# ardustat_discreet_resistors.net
KiCad netlist of a schematic drawn in EAGLE
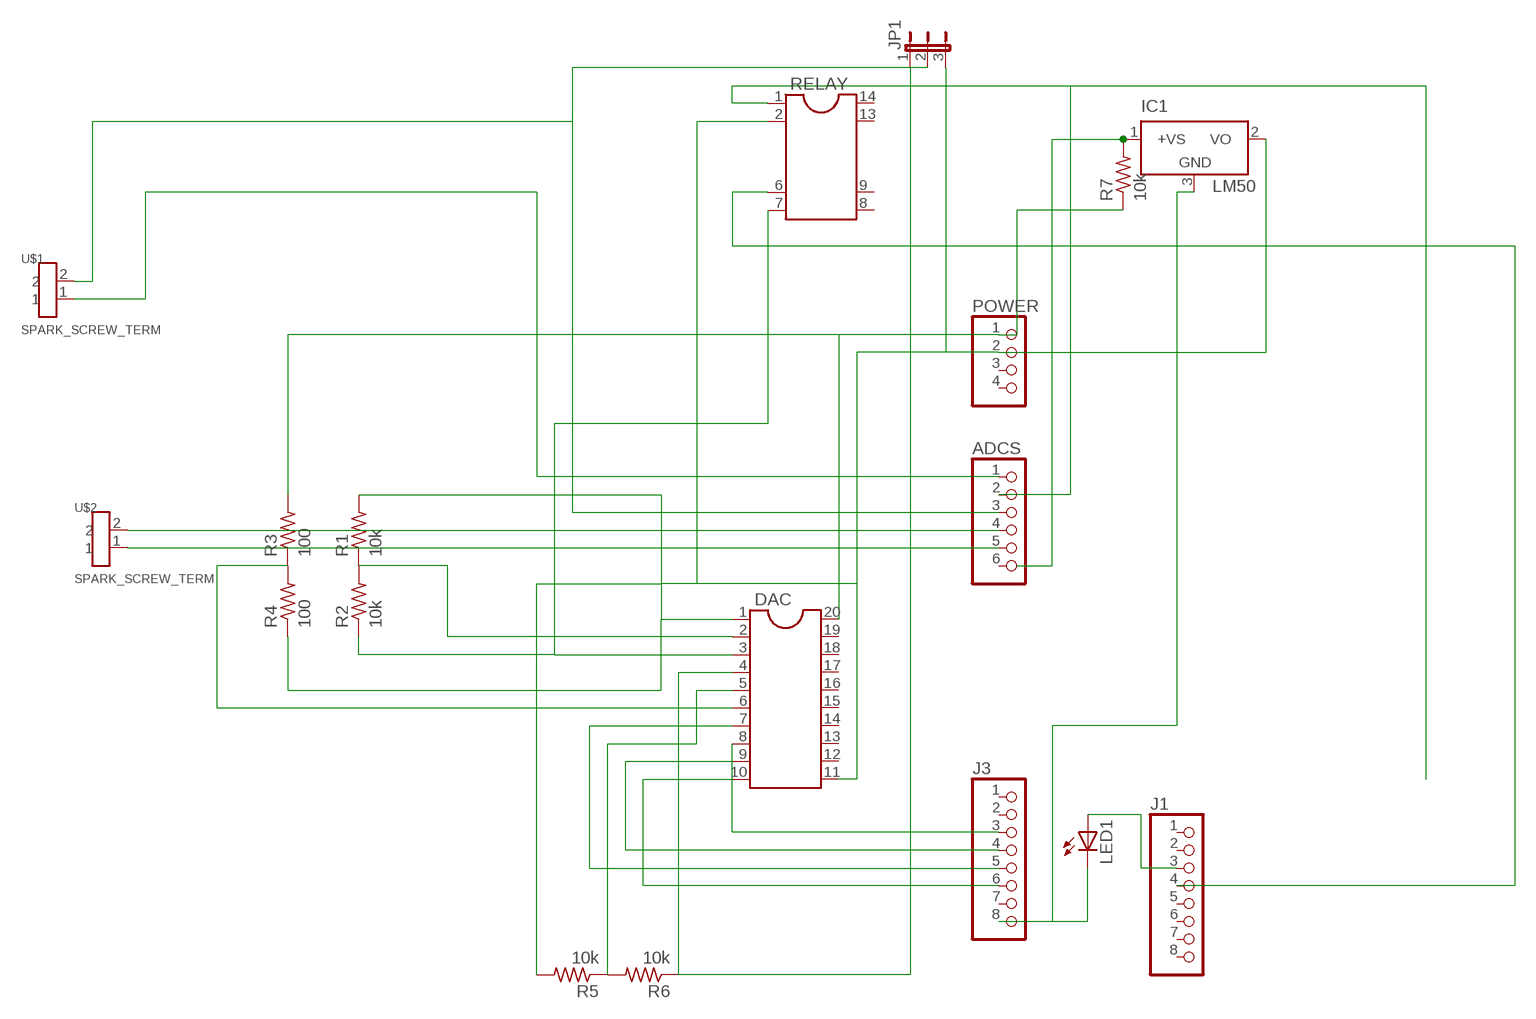
[diagram p0: schematic, sheet 1]

(export (version "E")
  (design (tool "Eeschema 10.0.6"))
  (components
    (comp (ref "ADCS")
      (value "PINHD-1X6")
      (footprint "eagle-import:1X06")
      (libsource (lib "eagle-import") (part "PINHD-1X6"))
    )
    (comp (ref "DAC")
      (value "DIL20S")
      (footprint "eagle-import:SOCKED-20")
      (libsource (lib "eagle-import") (part "DIL20S"))
    )
    (comp (ref "IC1")
      (value "LM50")
      (footprint "eagle-import:SOT23")
      (libsource (lib "eagle-import") (part "LM50"))
    )
    (comp (ref "J1")
      (value "PINHD-1X8")
      (footprint "eagle-import:1X08")
      (libsource (lib "eagle-import") (part "PINHD-1X8"))
    )
    (comp (ref "J3")
      (value "PINHD-1X8")
      (footprint "eagle-import:1X08")
      (libsource (lib "eagle-import") (part "PINHD-1X8"))
    )
    (comp (ref "JP1")
      (value "JP2E")
      (footprint "eagle-import:JP2")
      (libsource (lib "eagle-import") (part "JP2E"))
    )
    (comp (ref "LED1")
      (value "LED5MM")
      (footprint "eagle-import:LED5MM")
      (libsource (lib "eagle-import") (part "LED5MM"))
    )
    (comp (ref "POWER")
      (value "PINHD-1X4")
      (footprint "eagle-import:1X04")
      (libsource (lib "eagle-import") (part "PINHD-1X4"))
    )
    (comp (ref "R1")
      (value "10k")
      (footprint "eagle-import:0207_12")
      (libsource (lib "eagle-import") (part "R-US_0207/12"))
    )
    (comp (ref "R2")
      (value "10k")
      (footprint "eagle-import:0207_12")
      (libsource (lib "eagle-import") (part "R-US_0207/12"))
    )
    (comp (ref "R3")
      (value "100")
      (footprint "eagle-import:0207_12")
      (libsource (lib "eagle-import") (part "R-US_0207/12"))
    )
    (comp (ref "R4")
      (value "100")
      (footprint "eagle-import:0207_12")
      (libsource (lib "eagle-import") (part "R-US_0207/12"))
    )
    (comp (ref "R5")
      (value "10k")
      (footprint "eagle-import:0207_12")
      (libsource (lib "eagle-import") (part "R-US_0207/12"))
    )
    (comp (ref "R6")
      (value "10k")
      (footprint "eagle-import:0207_12")
      (libsource (lib "eagle-import") (part "R-US_0207/12"))
    )
    (comp (ref "R7")
      (value "10k")
      (footprint "eagle-import:0207_12")
      (libsource (lib "eagle-import") (part "R-US_0207/12"))
    )
    (comp (ref "RELAY")
      (value "DIL14/8")
      (footprint "eagle-import:DIL14_8")
      (libsource (lib "eagle-import") (part "DIL14/8"))
    )
    (comp (ref "U$1")
      (value "SPARK_SCREW_TERM")
      (footprint "eagle-import:SPARK_SCREW_TERM")
      (libsource (lib "eagle-import") (part "SPARK_SCREW_TERM"))
    )
    (comp (ref "U$2")
      (value "SPARK_SCREW_TERM")
      (footprint "eagle-import:SPARK_SCREW_TERM")
      (libsource (lib "eagle-import") (part "SPARK_SCREW_TERM"))
    )
  )
  (nets
    (net (code "1") (name "Net-(ADCS-Pad1)") (class "Default")
      (node (ref "ADCS") (pin "1") (pinfunction "1_1") (pintype "passive"))
      (node (ref "U$1") (pin "1") (pinfunction "1_1") (pintype "bidirectional"))
    )
    (net (code "2") (name "Net-(ADCS-Pad2)") (class "Default")
      (node (ref "ADCS") (pin "2") (pinfunction "2_2") (pintype "passive"))
      (node (ref "RELAY") (pin "1") (pinfunction "1_1") (pintype "passive"))
    )
    (net (code "3") (name "Net-(ADCS-Pad3)") (class "Default")
      (node (ref "ADCS") (pin "3") (pinfunction "3_3") (pintype "passive"))
      (node (ref "JP1") (pin "2") (pinfunction "2_2") (pintype "passive"))
      (node (ref "U$1") (pin "2") (pinfunction "2_2") (pintype "bidirectional"))
    )
    (net (code "4") (name "Net-(ADCS-Pad4)") (class "Default")
      (node (ref "ADCS") (pin "4") (pinfunction "4_4") (pintype "passive"))
      (node (ref "U$2") (pin "2") (pinfunction "2_2") (pintype "bidirectional"))
    )
    (net (code "5") (name "Net-(ADCS-Pad5)") (class "Default")
      (node (ref "ADCS") (pin "5") (pinfunction "5_5") (pintype "passive"))
      (node (ref "U$2") (pin "1") (pinfunction "1_1") (pintype "bidirectional"))
    )
    (net (code "6") (name "Net-(DAC-Pad2)") (class "Default")
      (node (ref "DAC") (pin "2") (pinfunction "2_2") (pintype "passive"))
      (node (ref "R1") (pin "1") (pinfunction "1_1") (pintype "passive"))
      (node (ref "R2") (pin "2") (pinfunction "2_2") (pintype "passive"))
    )
    (net (code "7") (name "Net-(DAC-Pad3)") (class "Default")
      (node (ref "DAC") (pin "3") (pinfunction "3_3") (pintype "passive"))
      (node (ref "R2") (pin "1") (pinfunction "1_1") (pintype "passive"))
      (node (ref "RELAY") (pin "7") (pinfunction "7_7") (pintype "passive"))
    )
    (net (code "8") (name "Net-(DAC-Pad4)") (class "Default")
      (node (ref "DAC") (pin "4") (pinfunction "4_4") (pintype "passive"))
      (node (ref "JP1") (pin "1") (pinfunction "1_1") (pintype "passive"))
      (node (ref "R6") (pin "1") (pinfunction "1_1") (pintype "passive"))
    )
    (net (code "9") (name "Net-(DAC-Pad5)") (class "Default")
      (node (ref "DAC") (pin "5") (pinfunction "5_5") (pintype "passive"))
      (node (ref "R5") (pin "1") (pinfunction "1_1") (pintype "passive"))
      (node (ref "R6") (pin "2") (pinfunction "2_2") (pintype "passive"))
    )
    (net (code "10") (name "Net-(DAC-Pad6)") (class "Default")
      (node (ref "DAC") (pin "6") (pinfunction "6_6") (pintype "passive"))
      (node (ref "R3") (pin "1") (pinfunction "1_1") (pintype "passive"))
      (node (ref "R4") (pin "2") (pinfunction "2_2") (pintype "passive"))
    )
    (net (code "11") (name "Net-(DAC-Pad7)") (class "Default")
      (node (ref "DAC") (pin "7") (pinfunction "7_7") (pintype "passive"))
      (node (ref "J3") (pin "5") (pinfunction "5_5") (pintype "passive"))
    )
    (net (code "12") (name "Net-(DAC-Pad8)") (class "Default")
      (node (ref "DAC") (pin "8") (pinfunction "8_8") (pintype "passive"))
      (node (ref "J3") (pin "3") (pinfunction "3_3") (pintype "passive"))
    )
    (net (code "13") (name "Net-(DAC-Pad9)") (class "Default")
      (node (ref "DAC") (pin "9") (pinfunction "9_9") (pintype "passive"))
      (node (ref "J3") (pin "4") (pinfunction "4_4") (pintype "passive"))
    )
    (net (code "14") (name "Net-(DAC-Pad10)") (class "Default")
      (node (ref "DAC") (pin "10") (pinfunction "10_10") (pintype "passive"))
      (node (ref "J3") (pin "6") (pinfunction "6_6") (pintype "passive"))
    )
    (net (code "15") (name "Net-(DAC-Pad20)") (class "Default")
      (node (ref "DAC") (pin "20") (pinfunction "20_20") (pintype "passive"))
      (node (ref "POWER") (pin "1") (pinfunction "1_1") (pintype "passive"))
      (node (ref "R3") (pin "2") (pinfunction "2_2") (pintype "passive"))
      (node (ref "R7") (pin "1") (pinfunction "1_1") (pintype "passive"))
    )
    (net (code "16") (name "Net-(IC1-+VS)") (class "Default")
      (node (ref "IC1") (pin "1") (pinfunction "+VS_1") (pintype "input"))
      (node (ref "R7") (pin "2") (pinfunction "2_2") (pintype "passive"))
    )
    (net (code "17") (name "Net-(IC1-GND)") (class "Default")
      (node (ref "IC1") (pin "3") (pinfunction "GND_3") (pintype "power_in"))
      (node (ref "J3") (pin "8") (pinfunction "8_8") (pintype "passive"))
      (node (ref "LED1") (pin "K") (pinfunction "C_K") (pintype "passive"))
    )
    (net (code "18") (name "Net-(IC1-VO)") (class "Default")
      (node (ref "DAC") (pin "1") (pinfunction "1_1") (pintype "passive"))
      (node (ref "DAC") (pin "11") (pinfunction "11_11") (pintype "passive"))
      (node (ref "IC1") (pin "2") (pinfunction "VO_2") (pintype "input"))
      (node (ref "JP1") (pin "3") (pinfunction "3_3") (pintype "passive"))
      (node (ref "POWER") (pin "2") (pinfunction "2_2") (pintype "passive"))
      (node (ref "R1") (pin "2") (pinfunction "2_2") (pintype "passive"))
      (node (ref "R4") (pin "1") (pinfunction "1_1") (pintype "passive"))
      (node (ref "R5") (pin "2") (pinfunction "2_2") (pintype "passive"))
      (node (ref "RELAY") (pin "2") (pinfunction "2_2") (pintype "passive"))
    )
    (net (code "19") (name "Net-(J1-Pad3)") (class "Default")
      (node (ref "J1") (pin "3") (pinfunction "3_3") (pintype "passive"))
      (node (ref "LED1") (pin "A") (pinfunction "A_A") (pintype "passive"))
    )
    (net (code "20") (name "Net-(J1-Pad4)") (class "Default")
      (node (ref "J1") (pin "4") (pinfunction "4_4") (pintype "passive"))
      (node (ref "RELAY") (pin "6") (pinfunction "6_6") (pintype "passive"))
    )
    (net (code "21") (name "unconnected-(ADCS-Pad6)") (class "Default")
      (node (ref "ADCS") (pin "6") (pinfunction "6_6") (pintype "passive"))
    )
    (net (code "22") (name "unconnected-(DAC-Pad12)") (class "Default")
      (node (ref "DAC") (pin "12") (pinfunction "12_12") (pintype "passive"))
    )
    (net (code "23") (name "unconnected-(DAC-Pad13)") (class "Default")
      (node (ref "DAC") (pin "13") (pinfunction "13_13") (pintype "passive"))
    )
    (net (code "24") (name "unconnected-(DAC-Pad14)") (class "Default")
      (node (ref "DAC") (pin "14") (pinfunction "14_14") (pintype "passive"))
    )
    (net (code "25") (name "unconnected-(DAC-Pad15)") (class "Default")
      (node (ref "DAC") (pin "15") (pinfunction "15_15") (pintype "passive"))
    )
    (net (code "26") (name "unconnected-(DAC-Pad16)") (class "Default")
      (node (ref "DAC") (pin "16") (pinfunction "16_16") (pintype "passive"))
    )
    (net (code "27") (name "unconnected-(DAC-Pad17)") (class "Default")
      (node (ref "DAC") (pin "17") (pinfunction "17_17") (pintype "passive"))
    )
    (net (code "28") (name "unconnected-(DAC-Pad18)") (class "Default")
      (node (ref "DAC") (pin "18") (pinfunction "18_18") (pintype "passive"))
    )
    (net (code "29") (name "unconnected-(DAC-Pad19)") (class "Default")
      (node (ref "DAC") (pin "19") (pinfunction "19_19") (pintype "passive"))
    )
    (net (code "30") (name "unconnected-(J1-Pad1)") (class "Default")
      (node (ref "J1") (pin "1") (pinfunction "1_1") (pintype "passive"))
    )
    (net (code "31") (name "unconnected-(J1-Pad2)") (class "Default")
      (node (ref "J1") (pin "2") (pinfunction "2_2") (pintype "passive"))
    )
    (net (code "32") (name "unconnected-(J1-Pad5)") (class "Default")
      (node (ref "J1") (pin "5") (pinfunction "5_5") (pintype "passive"))
    )
    (net (code "33") (name "unconnected-(J1-Pad6)") (class "Default")
      (node (ref "J1") (pin "6") (pinfunction "6_6") (pintype "passive"))
    )
    (net (code "34") (name "unconnected-(J1-Pad7)") (class "Default")
      (node (ref "J1") (pin "7") (pinfunction "7_7") (pintype "passive"))
    )
    (net (code "35") (name "unconnected-(J1-Pad8)") (class "Default")
      (node (ref "J1") (pin "8") (pinfunction "8_8") (pintype "passive"))
    )
    (net (code "36") (name "unconnected-(J3-Pad1)") (class "Default")
      (node (ref "J3") (pin "1") (pinfunction "1_1") (pintype "passive"))
    )
    (net (code "37") (name "unconnected-(J3-Pad2)") (class "Default")
      (node (ref "J3") (pin "2") (pinfunction "2_2") (pintype "passive"))
    )
    (net (code "38") (name "unconnected-(J3-Pad7)") (class "Default")
      (node (ref "J3") (pin "7") (pinfunction "7_7") (pintype "passive"))
    )
    (net (code "39") (name "unconnected-(POWER-Pad3)") (class "Default")
      (node (ref "POWER") (pin "3") (pinfunction "3_3") (pintype "passive"))
    )
    (net (code "40") (name "unconnected-(POWER-Pad4)") (class "Default")
      (node (ref "POWER") (pin "4") (pinfunction "4_4") (pintype "passive"))
    )
    (net (code "41") (name "unconnected-(RELAY-Pad8)") (class "Default")
      (node (ref "RELAY") (pin "8") (pinfunction "8_8") (pintype "passive"))
    )
    (net (code "42") (name "unconnected-(RELAY-Pad9)") (class "Default")
      (node (ref "RELAY") (pin "9") (pinfunction "9_9") (pintype "passive"))
    )
    (net (code "43") (name "unconnected-(RELAY-Pad13)") (class "Default")
      (node (ref "RELAY") (pin "13") (pinfunction "13_13") (pintype "passive"))
    )
    (net (code "44") (name "unconnected-(RELAY-Pad14)") (class "Default")
      (node (ref "RELAY") (pin "14") (pinfunction "14_14") (pintype "passive"))
    )
  )
)
